# USB.net
KiCad netlist of a schematic drawn in Altium Designer
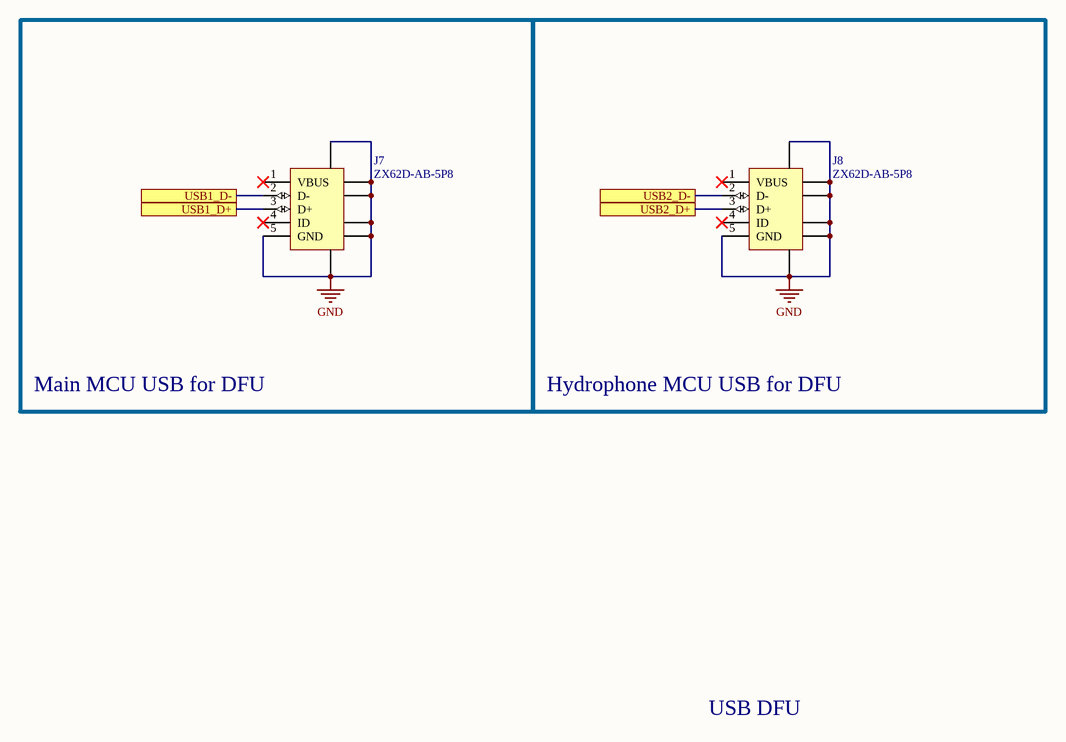
[diagram p0: USB.SchDoc]

(export (version "E")
  (design (tool "Eeschema 10.0.6"))
  (components
    (comp (ref "J7")
      (value "ZX62D-AB-5P8")
      (footprint "HIRO-ZX62D-AB-5P8_V")
      (fields (field (name "MANUFACTURER") "Hirose Electric"))
      (libsource (lib "Altium Content Vault") (part "HIRO-ZX62D-AB-5P8-5"))
    )
    (comp (ref "J8")
      (value "ZX62D-AB-5P8")
      (footprint "HIRO-ZX62D-AB-5P8_V")
      (fields (field (name "MANUFACTURER") "Hirose Electric"))
      (libsource (lib "Altium Content Vault") (part "HIRO-ZX62D-AB-5P8-5"))
    )
  )
  (nets
    (net (code "1") (name "/USB1_D+") (class "Default")
      (node (ref "J7") (pin "3") (pinfunction "D+_3") (pintype "bidirectional"))
    )
    (net (code "2") (name "/USB1_D-") (class "Default")
      (node (ref "J7") (pin "2") (pinfunction "D-_2") (pintype "bidirectional"))
    )
    (net (code "3") (name "/USB2_D+") (class "Default")
      (node (ref "J8") (pin "3") (pinfunction "D+_3") (pintype "bidirectional"))
    )
    (net (code "4") (name "/USB2_D-") (class "Default")
      (node (ref "J8") (pin "2") (pinfunction "D-_2") (pintype "bidirectional"))
    )
    (net (code "5") (name "GND") (class "Default")
      (node (ref "J7") (pin "10") (pinfunction "SHLD_10") (pintype "passive"))
      (node (ref "J7") (pin "11") (pinfunction "SHLD_11") (pintype "passive"))
      (node (ref "J7") (pin "5") (pinfunction "GND_5") (pintype "power_in"))
      (node (ref "J7") (pin "6") (pinfunction "SHLD_6") (pintype "passive"))
      (node (ref "J7") (pin "7") (pinfunction "SHLD_7") (pintype "passive"))
      (node (ref "J7") (pin "8") (pinfunction "SHLD_8") (pintype "passive"))
      (node (ref "J7") (pin "9") (pinfunction "SHLD_9") (pintype "passive"))
      (node (ref "J8") (pin "10") (pinfunction "SHLD_10") (pintype "passive"))
      (node (ref "J8") (pin "11") (pinfunction "SHLD_11") (pintype "passive"))
      (node (ref "J8") (pin "5") (pinfunction "GND_5") (pintype "power_in"))
      (node (ref "J8") (pin "6") (pinfunction "SHLD_6") (pintype "passive"))
      (node (ref "J8") (pin "7") (pinfunction "SHLD_7") (pintype "passive"))
      (node (ref "J8") (pin "8") (pinfunction "SHLD_8") (pintype "passive"))
      (node (ref "J8") (pin "9") (pinfunction "SHLD_9") (pintype "passive"))
    )
    (net (code "6") (name "unconnected-(J7-ID-Pad4)") (class "Default")
      (node (ref "J7") (pin "4") (pinfunction "ID_4") (pintype "passive+no_connect"))
    )
    (net (code "7") (name "unconnected-(J7-VBUS-Pad1)") (class "Default")
      (node (ref "J7") (pin "1") (pinfunction "VBUS_1") (pintype "power_in+no_connect"))
    )
    (net (code "8") (name "unconnected-(J8-ID-Pad4)") (class "Default")
      (node (ref "J8") (pin "4") (pinfunction "ID_4") (pintype "passive+no_connect"))
    )
    (net (code "9") (name "unconnected-(J8-VBUS-Pad1)") (class "Default")
      (node (ref "J8") (pin "1") (pinfunction "VBUS_1") (pintype "power_in+no_connect"))
    )
  )
)
